# 04_-_MICROCONTROLLER.net
KiCad netlist of a schematic drawn in Altium Designer
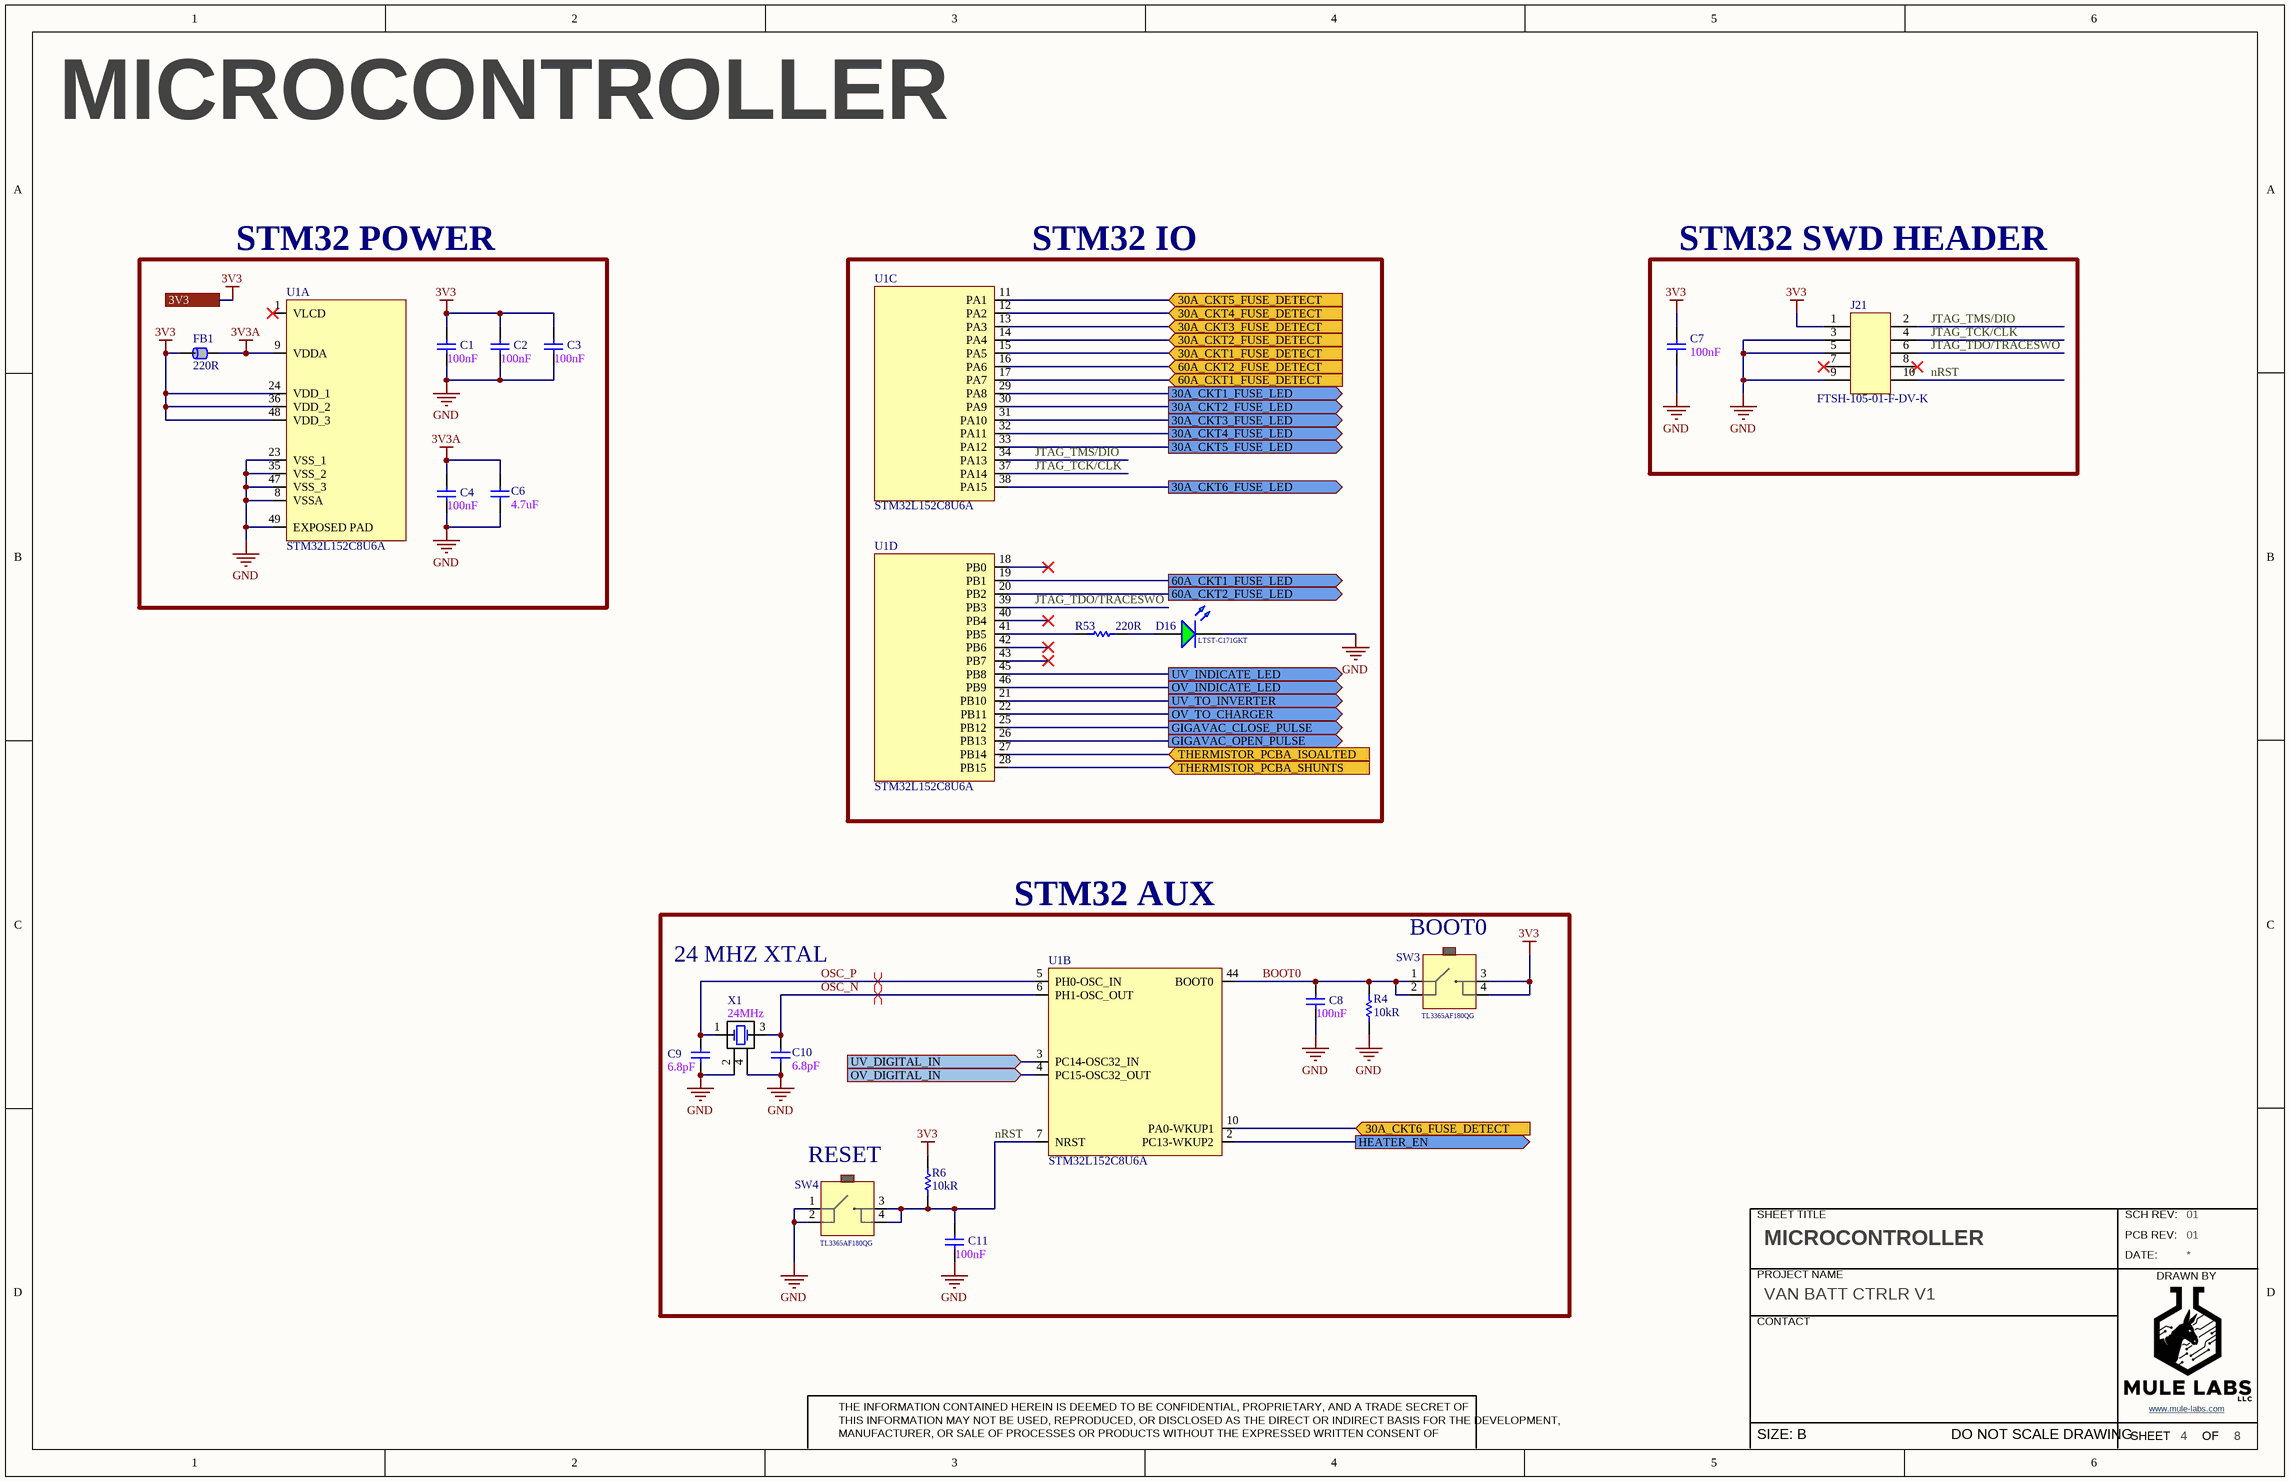
[diagram p0: [04] - MICROCONTROLLER.SchDoc]

(export (version "E")
  (design (tool "Eeschema 10.0.6"))
  (components
    (comp (ref "C1")
      (value "100nF")
      (footprint "INCH 0603 - METRIC 1608 - H090")
      (description "CAP CER 0.1UF 25V X7R 0603")
      (fields
        (field (name "MANUFACTURER") "TDK")
        (field (name "MANUFACTURER PART NUMBER") "CGA3E2X7R1E104K080AA")
      )
      (libsource (lib "Capacitors") (part "CGA3E2X7R1E104K080AA"))
    )
    (comp (ref "C2")
      (value "100nF")
      (footprint "INCH 0603 - METRIC 1608 - H090")
      (description "CAP CER 0.1UF 25V X7R 0603")
      (fields
        (field (name "MANUFACTURER") "TDK")
        (field (name "MANUFACTURER PART NUMBER") "CGA3E2X7R1E104K080AA")
      )
      (libsource (lib "Capacitors") (part "CGA3E2X7R1E104K080AA"))
    )
    (comp (ref "C3")
      (value "100nF")
      (footprint "INCH 0603 - METRIC 1608 - H090")
      (description "CAP CER 0.1UF 25V X7R 0603")
      (fields
        (field (name "MANUFACTURER") "TDK")
        (field (name "MANUFACTURER PART NUMBER") "CGA3E2X7R1E104K080AA")
      )
      (libsource (lib "Capacitors") (part "CGA3E2X7R1E104K080AA"))
    )
    (comp (ref "C4")
      (value "100nF")
      (footprint "INCH 0603 - METRIC 1608 - H090")
      (description "CAP CER 0.1UF 25V X7R 0603")
      (fields
        (field (name "MANUFACTURER") "TDK")
        (field (name "MANUFACTURER PART NUMBER") "CGA3E2X7R1E104K080AA")
      )
      (libsource (lib "Capacitors") (part "CGA3E2X7R1E104K080AA"))
    )
    (comp (ref "C6")
      (value "4.7uF")
      (footprint "INCH 0805 - METRIC 2012 - H145")
      (description "CAP CER 4.7UF 50V X7S 0805")
      (fields
        (field (name "MANUFACTURER") "Murata")
        (field (name "MANUFACTURER PART NUMBER") "GRM21BC71H475KE11L")
      )
      (libsource (lib "Capacitors") (part "GRM21BC71H475KE11L"))
    )
    (comp (ref "C7")
      (value "100nF")
      (footprint "INCH 0603 - METRIC 1608 - H090")
      (description "CAP CER 0.1UF 25V X7R 0603")
      (fields
        (field (name "MANUFACTURER") "TDK")
        (field (name "MANUFACTURER PART NUMBER") "CGA3E2X7R1E104K080AA")
      )
      (libsource (lib "Capacitors") (part "CGA3E2X7R1E104K080AA"))
    )
    (comp (ref "C8")
      (value "100nF")
      (footprint "INCH 0603 - METRIC 1608 - H090")
      (description "CAP CER 0.1UF 25V X7R 0603")
      (fields
        (field (name "MANUFACTURER") "TDK")
        (field (name "MANUFACTURER PART NUMBER") "CGA3E2X7R1E104K080AA")
      )
      (libsource (lib "Capacitors") (part "CGA3E2X7R1E104K080AA"))
    )
    (comp (ref "C9")
      (value "6.8pF")
      (footprint "INCH 0402 - METRIC 1005 - H055")
      (description "CAP CER 6.8PF 50V 0402")
      (fields
        (field (name "MANUFACTURER") "Murata")
        (field (name "MANUFACTURER PART NUMBER") "GJM1555C1H6R8WB01D")
      )
      (libsource (lib "Capacitors") (part "GJM1555C1H6R8WB01D"))
    )
    (comp (ref "C10")
      (value "6.8pF")
      (footprint "INCH 0402 - METRIC 1005 - H055")
      (description "CAP CER 6.8PF 50V 0402")
      (fields
        (field (name "MANUFACTURER") "Murata")
        (field (name "MANUFACTURER PART NUMBER") "GJM1555C1H6R8WB01D")
      )
      (libsource (lib "Capacitors") (part "GJM1555C1H6R8WB01D"))
    )
    (comp (ref "C11")
      (value "100nF")
      (footprint "INCH 0603 - METRIC 1608 - H090")
      (description "CAP CER 0.1UF 25V X7R 0603")
      (fields
        (field (name "MANUFACTURER") "TDK")
        (field (name "MANUFACTURER PART NUMBER") "CGA3E2X7R1E104K080AA")
      )
      (libsource (lib "Capacitors") (part "CGA3E2X7R1E104K080AA"))
    )
    (comp (ref "D16")
      (value "LTST-C171GKT")
      (footprint "LED - 0805 - GREEN")
      (fields (field (name "MANUFACTURER") "Vishay Lite-On"))
      (libsource (lib "LEDs") (part "LTST-C171GKT"))
    )
    (comp (ref "FB1")
      (value "220R")
      (footprint "INCH 0603 - METRIC 1608 - H100")
      (description "FERRITE BEAD 220 OHM 0603 1LN")
      (fields
        (field (name "MANUFACTURER") "Murata")
        (field (name "MANUFACTURER PART NUMBER") "BLM18EG221SN1D")
      )
      (libsource (lib "Ferrite Beads") (part "BLM18EG221SN1D"))
    )
    (comp (ref "J21")
      (value "FTSH-105-01-F-DV-K")
      (footprint "SAMTEC_FTSH-105-01-F-DV-K-P-TR")
      (description "1.27 mm, 2 Rows, 10 Contacts, Surface Mount")
      (fields (field (name "MANUFACTURER") "Samtec"))
      (libsource (lib "Connectors") (part "FTSH-105-01-F-DV-K"))
    )
    (comp (ref "R4")
      (value "10kR")
      (footprint "INCH 0603 - METRIC 1508 - H050")
      (description "RES SMD 10K OHM 5% 1/10W 0603")
      (fields
        (field (name "MANUFACTURER") "Vishay Dale")
        (field (name "MANUFACTURER PART NUMBER") "CRCW060310K0JNEA")
      )
      (libsource (lib "Resistors") (part "CRCW060310K0JNEA"))
    )
    (comp (ref "R6")
      (value "10kR")
      (footprint "INCH 0603 - METRIC 1508 - H050")
      (description "RES SMD 10K OHM 5% 1/10W 0603")
      (fields
        (field (name "MANUFACTURER") "Vishay Dale")
        (field (name "MANUFACTURER PART NUMBER") "CRCW060310K0JNEA")
      )
      (libsource (lib "Resistors") (part "CRCW060310K0JNEA"))
    )
    (comp (ref "R53")
      (value "220R")
      (footprint "INCH 0603 - METRIC 1608 - H055")
      (description "RES SMD 220 OHM 1% 1/10W 0603")
      (fields
        (field (name "MANUFACTURER") "Yageo")
        (field (name "MANUFACTURER PART NUMBER") "RC0603FR-07220RL")
      )
      (libsource (lib "Resistors") (part "RC0603FR-07220RL"))
    )
    (comp (ref "SW3")
      (value "TL3365AF180QG")
      (footprint "ESWITCH_TL3365AF180QG")
      (description "SWITCH TACTILE SPST-NO 0.05A 12V")
      (fields (field (name "MANUFACTURER") "E-Switch"))
      (libsource (lib "Switches") (part "TL3365AF180QG"))
    )
    (comp (ref "SW4")
      (value "TL3365AF180QG")
      (footprint "ESWITCH_TL3365AF180QG")
      (description "SWITCH TACTILE SPST-NO 0.05A 12V")
      (fields (field (name "MANUFACTURER") "E-Switch"))
      (libsource (lib "Switches") (part "TL3365AF180QG"))
    )
    (comp (ref "U1")
      (value "STM32L152C8U6A")
      (footprint "QFN49P50_700X700X60L40X25T560N")
      (description "IC MCU 32BIT 64KB FLASH 48UFQFPN")
      (fields (field (name "MANUFACTURER") "STMicroelectronics"))
      (libsource (lib "Microcontrollers") (part "STM32L152C8U6A"))
    )
    (comp (ref "X1")
      (value "NX2520SA-24.000000MHZ")
      (footprint "NX2520SA-24MHZ")
      (description "CRYSTAL 24.000000MHZ 10PF SMD")
      (fields (field (name "MANUFACTURER") "NDK") (field (name "FREQUENCY") "24MHz"))
      (libsource (lib "Crystals Oscillators Resonators") (part "NX2520SA-24MHZ"))
    )
  )
  (nets
    (net (code "1") (name "/30A_CKT1_FUSE_DETECT") (class "Default")
      (node (ref "U1") (pin "15") (pinfunction "PA5_15") (pintype "passive"))
    )
    (net (code "2") (name "/30A_CKT1_FUSE_LED") (class "Default")
      (node (ref "U1") (pin "29") (pinfunction "PA8_29") (pintype "passive"))
    )
    (net (code "3") (name "/30A_CKT2_FUSE_DETECT") (class "Default")
      (node (ref "U1") (pin "14") (pinfunction "PA4_14") (pintype "passive"))
    )
    (net (code "4") (name "/30A_CKT2_FUSE_LED") (class "Default")
      (node (ref "U1") (pin "30") (pinfunction "PA9_30") (pintype "passive"))
    )
    (net (code "5") (name "/30A_CKT3_FUSE_DETECT") (class "Default")
      (node (ref "U1") (pin "13") (pinfunction "PA3_13") (pintype "passive"))
    )
    (net (code "6") (name "/30A_CKT3_FUSE_LED") (class "Default")
      (node (ref "U1") (pin "31") (pinfunction "PA10_31") (pintype "passive"))
    )
    (net (code "7") (name "/30A_CKT4_FUSE_DETECT") (class "Default")
      (node (ref "U1") (pin "12") (pinfunction "PA2_12") (pintype "passive"))
    )
    (net (code "8") (name "/30A_CKT4_FUSE_LED") (class "Default")
      (node (ref "U1") (pin "32") (pinfunction "PA11_32") (pintype "passive"))
    )
    (net (code "9") (name "/30A_CKT5_FUSE_DETECT") (class "Default")
      (node (ref "U1") (pin "11") (pinfunction "PA1_11") (pintype "passive"))
    )
    (net (code "10") (name "/30A_CKT5_FUSE_LED") (class "Default")
      (node (ref "U1") (pin "33") (pinfunction "PA12_33") (pintype "passive"))
    )
    (net (code "11") (name "/30A_CKT6_FUSE_DETECT") (class "Default")
      (node (ref "U1") (pin "10") (pinfunction "PA0-WKUP1_10") (pintype "passive"))
    )
    (net (code "12") (name "/30A_CKT6_FUSE_LED") (class "Default")
      (node (ref "U1") (pin "38") (pinfunction "PA15_38") (pintype "passive"))
    )
    (net (code "13") (name "/60A_CKT1_FUSE_DETECT") (class "Default")
      (node (ref "U1") (pin "17") (pinfunction "PA7_17") (pintype "passive"))
    )
    (net (code "14") (name "/60A_CKT1_FUSE_LED") (class "Default")
      (node (ref "U1") (pin "19") (pinfunction "PB1_19") (pintype "passive"))
    )
    (net (code "15") (name "/60A_CKT2_FUSE_DETECT") (class "Default")
      (node (ref "U1") (pin "16") (pinfunction "PA6_16") (pintype "passive"))
    )
    (net (code "16") (name "/60A_CKT2_FUSE_LED") (class "Default")
      (node (ref "U1") (pin "20") (pinfunction "PB2_20") (pintype "passive"))
    )
    (net (code "17") (name "/BOOT0") (class "Default")
      (node (ref "C8") (pin "2") (pintype "passive"))
      (node (ref "R4") (pin "1") (pintype "passive"))
      (node (ref "SW3") (pin "1") (pinfunction "1_1") (pintype "passive"))
      (node (ref "SW3") (pin "2") (pinfunction "2_2") (pintype "passive"))
      (node (ref "U1") (pin "44") (pinfunction "BOOT0_44") (pintype "passive"))
    )
    (net (code "18") (name "/GIGAVAC_CLOSE_PULSE") (class "Default")
      (node (ref "U1") (pin "25") (pinfunction "PB12_25") (pintype "passive"))
    )
    (net (code "19") (name "/GIGAVAC_OPEN_PULSE") (class "Default")
      (node (ref "U1") (pin "26") (pinfunction "PB13_26") (pintype "passive"))
    )
    (net (code "20") (name "/HEATER_EN") (class "Default")
      (node (ref "U1") (pin "2") (pinfunction "PC13-WKUP2_2") (pintype "passive"))
    )
    (net (code "21") (name "/JTAG_TCK{slash}CLK") (class "Default")
      (node (ref "J21") (pin "4") (pinfunction "4_4") (pintype "passive"))
      (node (ref "U1") (pin "37") (pinfunction "PA14_37") (pintype "passive"))
    )
    (net (code "22") (name "/JTAG_TDO{slash}TRACESWO") (class "Default")
      (node (ref "J21") (pin "6") (pinfunction "6_6") (pintype "passive"))
      (node (ref "U1") (pin "39") (pinfunction "PB3_39") (pintype "passive"))
    )
    (net (code "23") (name "/JTAG_TMS{slash}DIO") (class "Default")
      (node (ref "J21") (pin "2") (pinfunction "2_2") (pintype "passive"))
      (node (ref "U1") (pin "34") (pinfunction "PA13_34") (pintype "passive"))
    )
    (net (code "24") (name "/OSC_N") (class "Default")
      (node (ref "C10") (pin "2") (pintype "passive"))
      (node (ref "U1") (pin "6") (pinfunction "PH1-OSC_OUT_6") (pintype "passive"))
      (node (ref "X1") (pin "3") (pinfunction "OSC2_3") (pintype "passive"))
    )
    (net (code "25") (name "/OSC_P") (class "Default")
      (node (ref "C9") (pin "2") (pintype "passive"))
      (node (ref "U1") (pin "5") (pinfunction "PH0-OSC_IN_5") (pintype "passive"))
      (node (ref "X1") (pin "1") (pinfunction "OSC1_1") (pintype "passive"))
    )
    (net (code "26") (name "/OV_DIGITAL_IN") (class "Default")
      (node (ref "U1") (pin "4") (pinfunction "PC15-OSC32_OUT_4") (pintype "passive"))
    )
    (net (code "27") (name "/OV_INDICATE_LED") (class "Default")
      (node (ref "U1") (pin "46") (pinfunction "PB9_46") (pintype "passive"))
    )
    (net (code "28") (name "/OV_TO_CHARGER") (class "Default")
      (node (ref "U1") (pin "22") (pinfunction "PB11_22") (pintype "passive"))
    )
    (net (code "29") (name "/THERMISTOR_PCBA_ISOALTED") (class "Default")
      (node (ref "U1") (pin "27") (pinfunction "PB14_27") (pintype "passive"))
    )
    (net (code "30") (name "/THERMISTOR_PCBA_SHUNTS") (class "Default")
      (node (ref "U1") (pin "28") (pinfunction "PB15_28") (pintype "passive"))
    )
    (net (code "31") (name "/UV_DIGITAL_IN") (class "Default")
      (node (ref "U1") (pin "3") (pinfunction "PC14-OSC32_IN_3") (pintype "passive"))
    )
    (net (code "32") (name "/UV_INDICATE_LED") (class "Default")
      (node (ref "U1") (pin "45") (pinfunction "PB8_45") (pintype "passive"))
    )
    (net (code "33") (name "/UV_TO_INVERTER") (class "Default")
      (node (ref "U1") (pin "21") (pinfunction "PB10_21") (pintype "passive"))
    )
    (net (code "34") (name "/nRST") (class "Default")
      (node (ref "C11") (pin "2") (pintype "passive"))
      (node (ref "J21") (pin "10") (pinfunction "10_10") (pintype "passive"))
      (node (ref "R6") (pin "2") (pintype "passive"))
      (node (ref "SW4") (pin "3") (pinfunction "3_3") (pintype "passive"))
      (node (ref "SW4") (pin "4") (pinfunction "4_4") (pintype "passive"))
      (node (ref "U1") (pin "7") (pinfunction "NRST_7") (pintype "passive"))
    )
    (net (code "35") (name "3V3") (class "Default")
      (node (ref "C1") (pin "2") (pintype "passive"))
      (node (ref "C2") (pin "2") (pintype "passive"))
      (node (ref "C3") (pin "2") (pintype "passive"))
      (node (ref "C7") (pin "2") (pintype "passive"))
      (node (ref "FB1") (pin "1") (pintype "passive"))
      (node (ref "J21") (pin "1") (pinfunction "1_1") (pintype "passive"))
      (node (ref "R6") (pin "1") (pintype "passive"))
      (node (ref "SW3") (pin "3") (pinfunction "3_3") (pintype "passive"))
      (node (ref "SW3") (pin "4") (pinfunction "4_4") (pintype "passive"))
      (node (ref "U1") (pin "24") (pinfunction "VDD_1_24") (pintype "passive"))
      (node (ref "U1") (pin "36") (pinfunction "VDD_2_36") (pintype "passive"))
      (node (ref "U1") (pin "48") (pinfunction "VDD_3_48") (pintype "passive"))
    )
    (net (code "36") (name "3V3A") (class "Default")
      (node (ref "C4") (pin "2") (pintype "passive"))
      (node (ref "C6") (pin "2") (pintype "passive"))
      (node (ref "FB1") (pin "2") (pintype "passive"))
      (node (ref "U1") (pin "9") (pinfunction "VDDA_9") (pintype "passive"))
    )
    (net (code "37") (name "GND") (class "Default")
      (node (ref "C1") (pin "1") (pintype "passive"))
      (node (ref "C10") (pin "1") (pintype "passive"))
      (node (ref "C11") (pin "1") (pintype "passive"))
      (node (ref "C2") (pin "1") (pintype "passive"))
      (node (ref "C3") (pin "1") (pintype "passive"))
      (node (ref "C4") (pin "1") (pintype "passive"))
      (node (ref "C6") (pin "1") (pintype "passive"))
      (node (ref "C7") (pin "1") (pintype "passive"))
      (node (ref "C8") (pin "1") (pintype "passive"))
      (node (ref "C9") (pin "1") (pintype "passive"))
      (node (ref "D16") (pin "C") (pintype "passive"))
      (node (ref "J21") (pin "3") (pinfunction "3_3") (pintype "passive"))
      (node (ref "J21") (pin "5") (pinfunction "5_5") (pintype "passive"))
      (node (ref "J21") (pin "9") (pinfunction "9_9") (pintype "passive"))
      (node (ref "R4") (pin "2") (pintype "passive"))
      (node (ref "SW4") (pin "1") (pinfunction "1_1") (pintype "passive"))
      (node (ref "SW4") (pin "2") (pinfunction "2_2") (pintype "passive"))
      (node (ref "U1") (pin "23") (pinfunction "VSS_1_23") (pintype "passive"))
      (node (ref "U1") (pin "35") (pinfunction "VSS_2_35") (pintype "passive"))
      (node (ref "U1") (pin "47") (pinfunction "VSS_3_47") (pintype "passive"))
      (node (ref "U1") (pin "49") (pinfunction "EXPOSED_PAD_49") (pintype "passive"))
      (node (ref "U1") (pin "8") (pinfunction "VSSA_8") (pintype "passive"))
      (node (ref "X1") (pin "2") (pinfunction "OSC2_2") (pintype "passive"))
      (node (ref "X1") (pin "4") (pinfunction "OSC2_4") (pintype "passive"))
    )
    (net (code "38") (name "Net-(D16-PadA)") (class "Default")
      (node (ref "D16") (pin "A") (pintype "passive"))
      (node (ref "R53") (pin "2") (pintype "passive"))
    )
    (net (code "39") (name "Net-(U1D-PB5)") (class "Default")
      (node (ref "R53") (pin "1") (pintype "passive"))
      (node (ref "U1") (pin "41") (pinfunction "PB5_41") (pintype "passive"))
    )
    (net (code "40") (name "unconnected-(J21-Pad7)") (class "Default")
      (node (ref "J21") (pin "7") (pinfunction "7_7") (pintype "passive+no_connect"))
    )
    (net (code "41") (name "unconnected-(J21-Pad8)") (class "Default")
      (node (ref "J21") (pin "8") (pinfunction "8_8") (pintype "passive+no_connect"))
    )
    (net (code "42") (name "unconnected-(U1A-VLCD-Pad1)") (class "Default")
      (node (ref "U1") (pin "1") (pinfunction "VLCD_1") (pintype "passive+no_connect"))
    )
    (net (code "43") (name "unconnected-(U1D-PB0-Pad18)") (class "Default")
      (node (ref "U1") (pin "18") (pinfunction "PB0_18") (pintype "passive+no_connect"))
    )
    (net (code "44") (name "unconnected-(U1D-PB4-Pad40)") (class "Default")
      (node (ref "U1") (pin "40") (pinfunction "PB4_40") (pintype "passive+no_connect"))
    )
    (net (code "45") (name "unconnected-(U1D-PB6-Pad42)") (class "Default")
      (node (ref "U1") (pin "42") (pinfunction "PB6_42") (pintype "passive+no_connect"))
    )
    (net (code "46") (name "unconnected-(U1D-PB7-Pad43)") (class "Default")
      (node (ref "U1") (pin "43") (pinfunction "PB7_43") (pintype "passive+no_connect"))
    )
  )
)
